# Louver_Control.net
KiCad netlist of a schematic drawn in Altium Designer
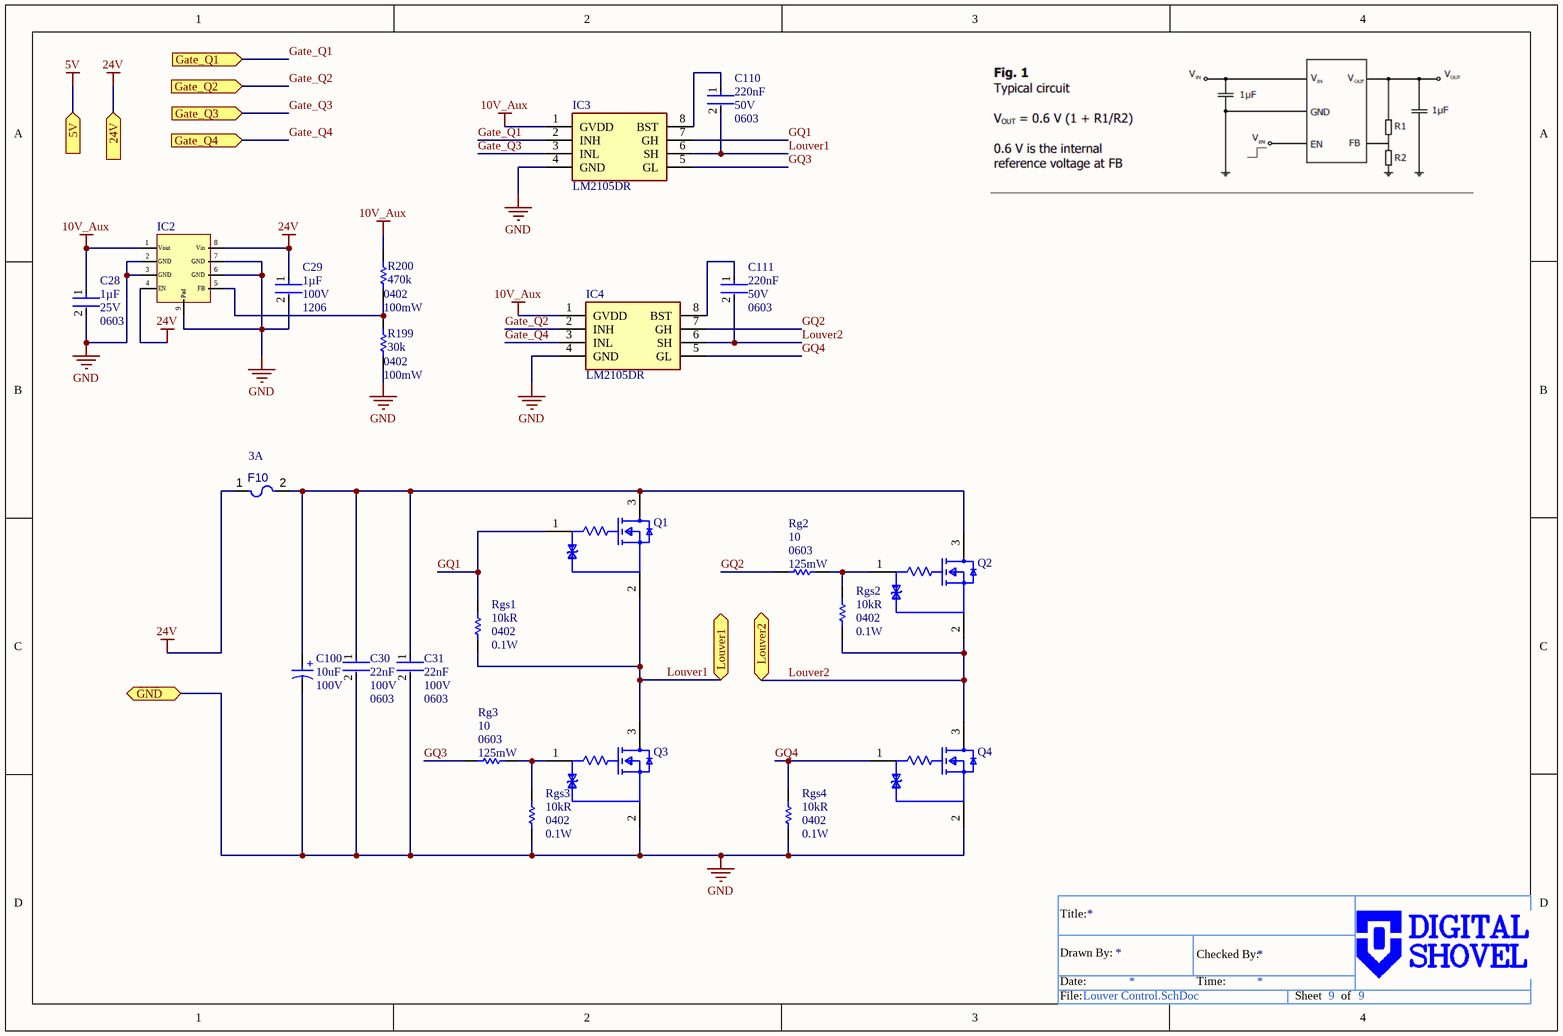
[diagram p0: Louver Control.SchDoc]

(export (version "E")
  (design (tool "Eeschema 10.0.6"))
  (components
    (comp (ref "C28")
      (value "1µF")
      (footprint "FP-CL10-IPC_A")
      (fields
        (field (name "VOLTAGE RATING") "25V")
        (field (name "CASE/PACKAGE") "0603")
        (field (name "Comment") "CL10B105KA8NNNC")
      )
      (libsource (lib "Digital Shovel") (part "CL10B105KA8NNNC"))
    )
    (comp (ref "C29")
      (value "1µF")
      (footprint "FP-CL31-IPC_A")
      (fields
        (field (name "VOLTAGE RATING") "100V")
        (field (name "CASE/PACKAGE") "1206")
        (field (name "Comment") "CL31B105KCHSNNE")
      )
      (libsource (lib "Digital Shovel") (part "b4654b650e69147ec39a6b967a45e02"))
    )
    (comp (ref "C30")
      (value "22nF")
      (footprint "FP-C0603C-CF-IPC_A")
      (description "Ceramic Capacitor, Ceramic, 100V, 10% +Tol, 10% -Tol, X7R, 15% TC, 0.022uF, Surface Mount, 0603")
      (fields
        (field (name "VOLTAGE RATING") "100V")
        (field (name "CASE/PACKAGE") "0603")
        (field (name "Comment") "C0603C223K1RACAUTO")
      )
      (libsource (lib "Digital Shovel") (part "b4654b650e69147ec39a6b967a45e02"))
    )
    (comp (ref "C31")
      (value "22nF")
      (footprint "FP-C0603C-CF-IPC_A")
      (description "Ceramic Capacitor, Ceramic, 100V, 10% +Tol, 10% -Tol, X7R, 15% TC, 0.022uF, Surface Mount, 0603")
      (fields
        (field (name "VOLTAGE RATING") "100V")
        (field (name "CASE/PACKAGE") "0603")
        (field (name "Comment") "C0603C223K1RACAUTO")
      )
      (libsource (lib "Digital Shovel") (part "b4654b650e69147ec39a6b967a45e02"))
    )
    (comp (ref "C100")
      (value "10uF")
      (footprint "WCAP-ASLL_D6.3H7.7")
      (description "Cap, 10Uf, 100V, Alu Elec, Smd, Radial Rohs Compliant: Yes")
      (fields (field (name "VOLTAGE RATING") "100V") (field (name "Comment") "865060845002"))
      (libsource (lib "Digital Shovel") (part "Capacitor_Polarized"))
    )
    (comp (ref "C110")
      (value "220nF")
      (footprint "FP-CL10-IPC_A")
      (fields
        (field (name "VOLTAGE RATING") "50V")
        (field (name "CASE/PACKAGE") "0603")
        (field (name "Comment") "CL10B224KB8VPNC")
      )
      (libsource (lib "Digital Shovel") (part "b4654b650e69147ec39a6b967a45e02"))
    )
    (comp (ref "C111")
      (value "220nF")
      (footprint "FP-CL10-IPC_A")
      (fields
        (field (name "VOLTAGE RATING") "50V")
        (field (name "CASE/PACKAGE") "0603")
        (field (name "Comment") "CL10B224KB8VPNC")
      )
      (libsource (lib "Digital Shovel") (part "b4654b650e69147ec39a6b967a45e02"))
    )
    (comp (ref "F10")
      (value "0679H3000-05")
      (footprint "0679H3000-05-Footprint-1")
      (description "Electric Fuse, Very Fast Blow, 3A, 350VAC, 72VDC, 50A (IR), Surface Mount, 2410")
      (fields (field (name "CURRENT RATING") "3A"))
      (libsource (lib "Digital Shovel") (part "FUSE-2"))
    )
    (comp (ref "IC2")
      (value "LDI55-ADEEN")
      (footprint "LDI55-ADEEN-Footprint-1")
      (description "Linear Voltage Regulator IC Positive Adjustable 1 Output 1A 8-ESOP")
      (libsource (lib "Digital Shovel") (part "LDI55-ADEEN-Symbol-1"))
    )
    (comp (ref "IC3")
      (value "LM2105DR")
      (footprint "LM2105DR-Footprint-1")
      (libsource (lib "Digital Shovel") (part "LM2105DR-Symbol-1"))
    )
    (comp (ref "IC4")
      (value "LM2105DR")
      (footprint "LM2105DR-Footprint-1")
      (libsource (lib "Digital Shovel") (part "LM2105DR-Symbol-1"))
    )
    (comp (ref "Q1")
      (value "SSM3K361R,LF")
      (footprint "FP-2-3Z1S-MFG")
      (description "N-Channel 100 V 3.5A (Ta) 1.2W (Ta) Surface Mount SOT-23F")
      (libsource (lib "Digital Shovel") (part "41947725386cc264758c98f2c26ea38"))
    )
    (comp (ref "Q2")
      (value "SSM3K361R,LF")
      (footprint "FP-2-3Z1S-MFG")
      (description "N-Channel 100 V 3.5A (Ta) 1.2W (Ta) Surface Mount SOT-23F")
      (libsource (lib "Digital Shovel") (part "41947725386cc264758c98f2c26ea38"))
    )
    (comp (ref "Q3")
      (value "SSM3K361R,LF")
      (footprint "FP-2-3Z1S-MFG")
      (description "N-Channel 100 V 3.5A (Ta) 1.2W (Ta) Surface Mount SOT-23F")
      (libsource (lib "Digital Shovel") (part "41947725386cc264758c98f2c26ea38"))
    )
    (comp (ref "Q4")
      (value "SSM3K361R,LF")
      (footprint "FP-2-3Z1S-MFG")
      (description "N-Channel 100 V 3.5A (Ta) 1.2W (Ta) Surface Mount SOT-23F")
      (libsource (lib "Digital Shovel") (part "41947725386cc264758c98f2c26ea38"))
    )
    (comp (ref "R199")
      (value "30k")
      (footprint "RESC1005X40X25LL10T10")
      (fields
        (field (name "POWER") "100mW")
        (field (name "TOLERANCE") "1%")
        (field (name "CASE/PACKAGE") "0402")
        (field (name "Comment") "RK73H1ETTP3002F")
      )
      (libsource (lib "Digital Shovel") (part "RES"))
    )
    (comp (ref "R200")
      (value "470k")
      (footprint "RESC1005X40X25LL10T10")
      (fields
        (field (name "TOLERANCE") "1%")
        (field (name "CASE/PACKAGE") "0402")
        (field (name "POWER") "100mW")
        (field (name "Comment") "RK73H1ETTP4703F")
      )
      (libsource (lib "Digital Shovel") (part "RES"))
    )
    (comp (ref "Rg2")
      (value "10")
      (footprint "FP-RK73H1J-IPC_A")
      (fields
        (field (name "CASE/PACKAGE") "0603")
        (field (name "POWER") "125mW")
        (field (name "TOLERANCE") "1%")
        (field (name "Comment") "RK73H1JTTDD10R0F")
      )
      (libsource (lib "Digital Shovel") (part "RES"))
    )
    (comp (ref "Rg3")
      (value "10")
      (footprint "FP-RK73H1J-IPC_A")
      (fields
        (field (name "CASE/PACKAGE") "0603")
        (field (name "POWER") "125mW")
        (field (name "TOLERANCE") "1%")
        (field (name "Comment") "RK73H1JTTDD10R0F")
      )
      (libsource (lib "Digital Shovel") (part "RES"))
    )
    (comp (ref "Rgs1")
      (value "10kR")
      (footprint "RESC1005X40X25LL10T10")
      (fields
        (field (name "PACKAGE") "0402")
        (field (name "POWER RATING") "0.1W")
        (field (name "Comment") "RK73H1ETTP1002F")
      )
      (libsource (lib "Digital Shovel") (part "RES"))
    )
    (comp (ref "Rgs2")
      (value "10kR")
      (footprint "RESC1005X40X25LL10T10")
      (fields
        (field (name "PACKAGE") "0402")
        (field (name "POWER RATING") "0.1W")
        (field (name "Comment") "RK73H1ETTP1002F")
      )
      (libsource (lib "Digital Shovel") (part "RES"))
    )
    (comp (ref "Rgs3")
      (value "10kR")
      (footprint "RESC1005X40X25LL10T10")
      (fields
        (field (name "PACKAGE") "0402")
        (field (name "POWER RATING") "0.1W")
        (field (name "Comment") "RK73H1ETTP1002F")
      )
      (libsource (lib "Digital Shovel") (part "RES"))
    )
    (comp (ref "Rgs4")
      (value "10kR")
      (footprint "RESC1005X40X25LL10T10")
      (fields
        (field (name "PACKAGE") "0402")
        (field (name "POWER RATING") "0.1W")
        (field (name "Comment") "RK73H1ETTP1002F")
      )
      (libsource (lib "Digital Shovel") (part "RES"))
    )
  )
  (nets
    (net (code "1") (name "/GQ1") (class "Default")
      (node (ref "IC3") (pin "7") (pinfunction "GH_7") (pintype "passive"))
      (node (ref "Q1") (pin "1") (pinfunction "Gate_1") (pintype "passive"))
      (node (ref "Rgs1") (pin "2") (pinfunction "2_2") (pintype "passive"))
    )
    (net (code "2") (name "/GQ2") (class "Default")
      (node (ref "IC4") (pin "7") (pinfunction "GH_7") (pintype "passive"))
      (node (ref "Rg2") (pin "1") (pinfunction "1_1") (pintype "passive"))
    )
    (net (code "3") (name "/GQ3") (class "Default")
      (node (ref "IC3") (pin "5") (pinfunction "GL_5") (pintype "passive"))
      (node (ref "Rg3") (pin "1") (pinfunction "1_1") (pintype "passive"))
    )
    (net (code "4") (name "/GQ4") (class "Default")
      (node (ref "IC4") (pin "5") (pinfunction "GL_5") (pintype "passive"))
      (node (ref "Q4") (pin "1") (pinfunction "Gate_1") (pintype "passive"))
      (node (ref "Rgs4") (pin "2") (pinfunction "2_2") (pintype "passive"))
    )
    (net (code "5") (name "/Gate_Q1") (class "Default")
      (node (ref "IC3") (pin "2") (pinfunction "INH_2") (pintype "passive"))
    )
    (net (code "6") (name "/Gate_Q2") (class "Default")
      (node (ref "IC4") (pin "2") (pinfunction "INH_2") (pintype "passive"))
    )
    (net (code "7") (name "/Gate_Q3") (class "Default")
      (node (ref "IC3") (pin "3") (pinfunction "INL_3") (pintype "passive"))
    )
    (net (code "8") (name "/Gate_Q4") (class "Default")
      (node (ref "IC4") (pin "3") (pinfunction "INL_3") (pintype "passive"))
    )
    (net (code "9") (name "/Louver1") (class "Default")
      (node (ref "C110") (pin "2") (pinfunction "2_2") (pintype "passive"))
      (node (ref "IC3") (pin "6") (pinfunction "SH_6") (pintype "passive"))
      (node (ref "Q1") (pin "2") (pinfunction "Source_2") (pintype "passive"))
      (node (ref "Q3") (pin "3") (pinfunction "Drain_3") (pintype "passive"))
      (node (ref "Rgs1") (pin "1") (pinfunction "1_1") (pintype "passive"))
    )
    (net (code "10") (name "/Louver2") (class "Default")
      (node (ref "C111") (pin "2") (pinfunction "2_2") (pintype "passive"))
      (node (ref "IC4") (pin "6") (pinfunction "SH_6") (pintype "passive"))
      (node (ref "Q2") (pin "2") (pinfunction "Source_2") (pintype "passive"))
      (node (ref "Q4") (pin "3") (pinfunction "Drain_3") (pintype "passive"))
      (node (ref "Rgs2") (pin "1") (pinfunction "1_1") (pintype "passive"))
    )
    (net (code "12") (name "10V_Aux") (class "Default")
      (node (ref "C28") (pin "1") (pinfunction "1_1") (pintype "passive"))
      (node (ref "IC2") (pin "1") (pinfunction "Vout_1") (pintype "passive"))
      (node (ref "IC3") (pin "1") (pinfunction "GVDD_1") (pintype "passive"))
      (node (ref "IC4") (pin "1") (pinfunction "GVDD_1") (pintype "passive"))
      (node (ref "R200") (pin "2") (pinfunction "2_2") (pintype "passive"))
    )
    (net (code "13") (name "24V") (class "Default")
      (node (ref "C29") (pin "1") (pinfunction "1_1") (pintype "passive"))
      (node (ref "F10") (pin "1") (pinfunction "1_1") (pintype "passive"))
      (node (ref "IC2") (pin "4") (pinfunction "EN_4") (pintype "passive"))
      (node (ref "IC2") (pin "8") (pinfunction "Vin_8") (pintype "passive"))
    )
    (net (code "14") (name "GND") (class "Default")
      (node (ref "C100") (pin "2") (pinfunction "N_2") (pintype "passive"))
      (node (ref "C28") (pin "2") (pinfunction "2_2") (pintype "passive"))
      (node (ref "C29") (pin "2") (pinfunction "2_2") (pintype "passive"))
      (node (ref "C30") (pin "2") (pinfunction "2_2") (pintype "passive"))
      (node (ref "C31") (pin "2") (pinfunction "2_2") (pintype "passive"))
      (node (ref "IC2") (pin "2") (pinfunction "GND_2") (pintype "passive"))
      (node (ref "IC2") (pin "3") (pinfunction "GND_3") (pintype "passive"))
      (node (ref "IC2") (pin "6") (pinfunction "GND_6") (pintype "passive"))
      (node (ref "IC2") (pin "7") (pinfunction "GND_7") (pintype "passive"))
      (node (ref "IC2") (pin "9") (pinfunction "Pad_9") (pintype "passive"))
      (node (ref "IC3") (pin "4") (pinfunction "GND_4") (pintype "passive"))
      (node (ref "IC4") (pin "4") (pinfunction "GND_4") (pintype "passive"))
      (node (ref "Q3") (pin "2") (pinfunction "Source_2") (pintype "passive"))
      (node (ref "Q4") (pin "2") (pinfunction "Source_2") (pintype "passive"))
      (node (ref "R199") (pin "1") (pinfunction "1_1") (pintype "passive"))
      (node (ref "Rgs3") (pin "1") (pinfunction "1_1") (pintype "passive"))
      (node (ref "Rgs4") (pin "1") (pinfunction "1_1") (pintype "passive"))
    )
    (net (code "15") (name "Net-(C100-P)") (class "Default")
      (node (ref "C100") (pin "1") (pinfunction "P_1") (pintype "passive"))
      (node (ref "C30") (pin "1") (pinfunction "1_1") (pintype "passive"))
      (node (ref "C31") (pin "1") (pinfunction "1_1") (pintype "passive"))
      (node (ref "F10") (pin "2") (pinfunction "2_2") (pintype "passive"))
      (node (ref "Q1") (pin "3") (pinfunction "Drain_3") (pintype "passive"))
      (node (ref "Q2") (pin "3") (pinfunction "Drain_3") (pintype "passive"))
    )
    (net (code "16") (name "Net-(IC2-FB)") (class "Default")
      (node (ref "IC2") (pin "5") (pinfunction "FB_5") (pintype "passive"))
      (node (ref "R199") (pin "2") (pinfunction "2_2") (pintype "passive"))
      (node (ref "R200") (pin "1") (pinfunction "1_1") (pintype "passive"))
    )
    (net (code "17") (name "Net-(IC3-BST)") (class "Default")
      (node (ref "C110") (pin "1") (pinfunction "1_1") (pintype "passive"))
      (node (ref "IC3") (pin "8") (pinfunction "BST_8") (pintype "passive"))
    )
    (net (code "18") (name "Net-(IC4-BST)") (class "Default")
      (node (ref "C111") (pin "1") (pinfunction "1_1") (pintype "passive"))
      (node (ref "IC4") (pin "8") (pinfunction "BST_8") (pintype "passive"))
    )
    (net (code "19") (name "Net-(Q2-Gate)") (class "Default")
      (node (ref "Q2") (pin "1") (pinfunction "Gate_1") (pintype "passive"))
      (node (ref "Rg2") (pin "2") (pinfunction "2_2") (pintype "passive"))
      (node (ref "Rgs2") (pin "2") (pinfunction "2_2") (pintype "passive"))
    )
    (net (code "20") (name "Net-(Q3-Gate)") (class "Default")
      (node (ref "Q3") (pin "1") (pinfunction "Gate_1") (pintype "passive"))
      (node (ref "Rg3") (pin "2") (pinfunction "2_2") (pintype "passive"))
      (node (ref "Rgs3") (pin "2") (pinfunction "2_2") (pintype "passive"))
    )
  )
)
